# MICHAv40.net
KiCad netlist of a schematic drawn in EAGLE
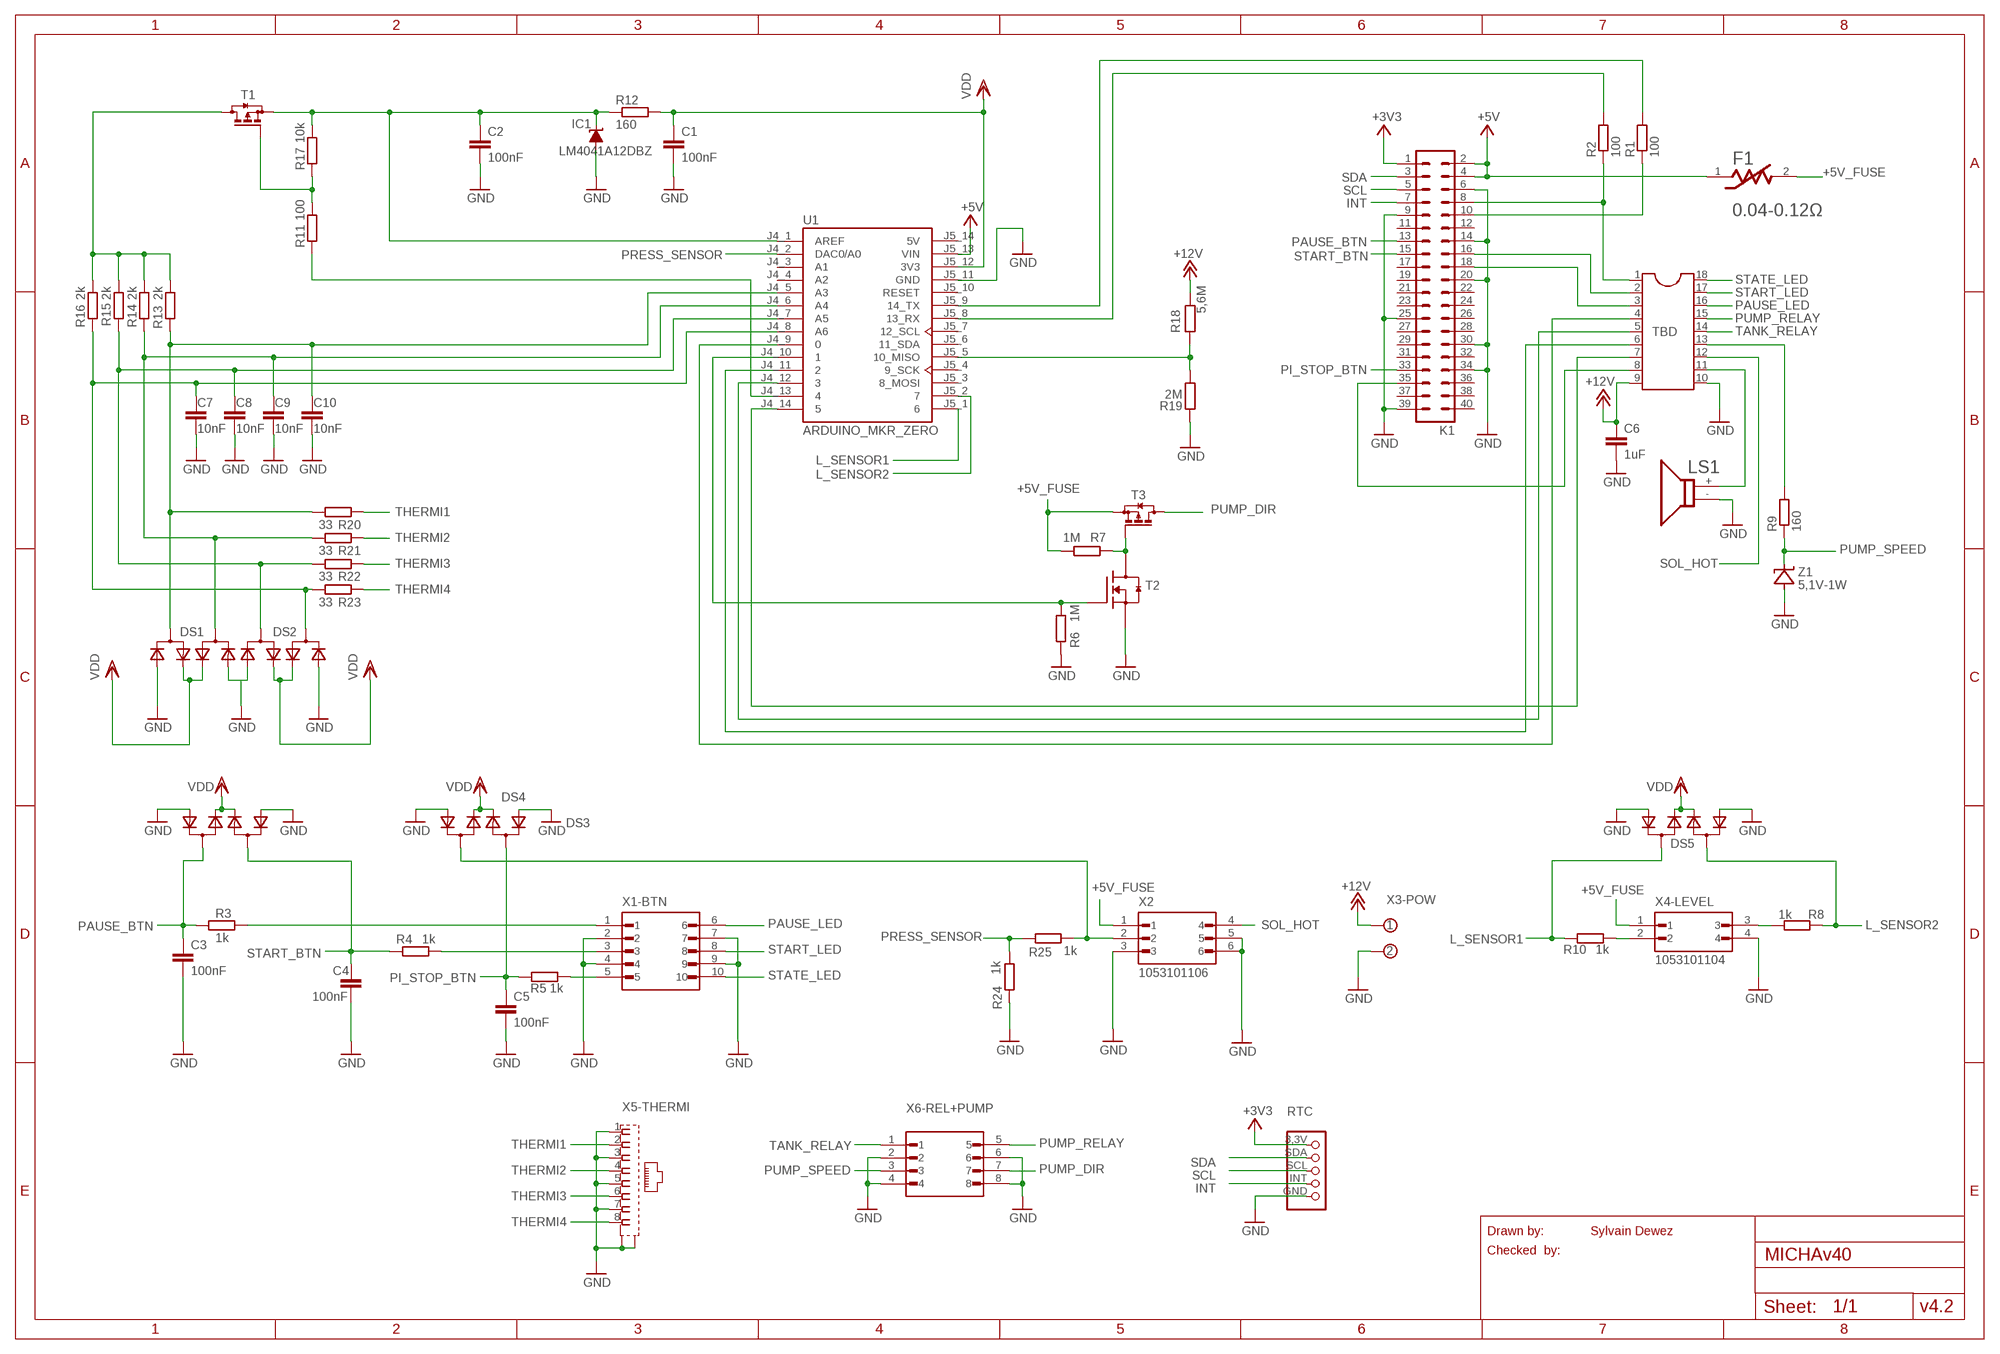
[diagram p0: schematic, sheet 1]

(export (version "E")
  (design (tool "Eeschema 10.0.6"))
  (components
    (comp (ref "C1")
      (value "100nF")
      (footprint "eagle-import:C1206")
      (libsource (lib "eagle-import") (part "C-EUC1206"))
    )
    (comp (ref "C2")
      (value "100nF")
      (footprint "eagle-import:C1206")
      (libsource (lib "eagle-import") (part "C-EUC1206"))
    )
    (comp (ref "C3")
      (value "100nF")
      (footprint "eagle-import:C1206")
      (libsource (lib "eagle-import") (part "C-EUC1206"))
    )
    (comp (ref "C4")
      (value "100nF")
      (footprint "eagle-import:C1206")
      (libsource (lib "eagle-import") (part "C-EUC1206"))
    )
    (comp (ref "C5")
      (value "100nF")
      (footprint "eagle-import:C1206")
      (libsource (lib "eagle-import") (part "C-EUC1206"))
    )
    (comp (ref "C6")
      (value "1uF")
      (footprint "eagle-import:C1206")
      (libsource (lib "eagle-import") (part "C-EUC1206"))
    )
    (comp (ref "C7")
      (value "10nF")
      (footprint "eagle-import:C1206")
      (libsource (lib "eagle-import") (part "C-EUC1206"))
    )
    (comp (ref "C8")
      (value "10nF")
      (footprint "eagle-import:C1206")
      (libsource (lib "eagle-import") (part "C-EUC1206"))
    )
    (comp (ref "C9")
      (value "10nF")
      (footprint "eagle-import:C1206")
      (libsource (lib "eagle-import") (part "C-EUC1206"))
    )
    (comp (ref "C10")
      (value "10nF")
      (footprint "eagle-import:C1206")
      (libsource (lib "eagle-import") (part "C-EUC1206"))
    )
    (comp (ref "DS1")
      (value "CMXSH2-4LSTRPBFREE")
      (footprint "eagle-import:CMXSH2-4LSTRPBFREE")
      (libsource (lib "eagle-import") (part "CMXSH2-4LSTRPBFREE"))
    )
    (comp (ref "DS2")
      (value "CMXSH2-4LSTRPBFREE")
      (footprint "eagle-import:CMXSH2-4LSTRPBFREE")
      (libsource (lib "eagle-import") (part "CMXSH2-4LSTRPBFREE"))
    )
    (comp (ref "DS3")
      (value "CMXSH2-4LSTRPBFREE")
      (footprint "eagle-import:CMXSH2-4LSTRPBFREE")
      (libsource (lib "eagle-import") (part "CMXSH2-4LSTRPBFREE"))
    )
    (comp (ref "DS4")
      (value "CMXSH2-4LSTRPBFREE")
      (footprint "eagle-import:CMXSH2-4LSTRPBFREE")
      (libsource (lib "eagle-import") (part "CMXSH2-4LSTRPBFREE"))
    )
    (comp (ref "DS5")
      (value "CMXSH2-4LSTRPBFREE")
      (footprint "eagle-import:CMXSH2-4LSTRPBFREE")
      (libsource (lib "eagle-import") (part "CMXSH2-4LSTRPBFREE"))
    )
    (comp (ref "F1")
      (value "LITTELFUSE_INC_1206L150THWRLITTELFUSE_INC_1206L150THWR_0_0")
      (footprint "eagle-import:LITTELFUSE_INC_1206L150THWR_0")
      (fields
        (field (name "DIGIKEY_PART_NUMBER") "F3372CT-ND")
        (field (name "MF") "Littelfuse Inc")
        (field (name "MOUSER_PART_NUMBER") "576-1206L150THWR")
      )
      (libsource (lib "eagle-import") (part "LITTELFUSE_INC_1206L150THWRLITTELFUSE_INC_1206L150THWR_0_0"))
    )
    (comp (ref "IC1")
      (value "LM4041A12DBZ")
      (footprint "eagle-import:DBZ_R-PDSO-G3")
      (fields (field (name "MPN") "LM4041A12IDBZR"))
      (libsource (lib "eagle-import") (part "LM4041DBZA12"))
    )
    (comp (ref "K1")
      (value "PIN20X2")
      (footprint "eagle-import:PIN_20X2")
      (libsource (lib "eagle-import") (part "PIN20X2"))
    )
    (comp (ref "LS1")
      (value "RSPRO-BUZZER-7800743")
      (footprint "eagle-import:RSPRO-BUZZER-7800743")
      (libsource (lib "eagle-import") (part "RSPRO-BUZZER-7800743"))
    )
    (comp (ref "R1")
      (value "100")
      (footprint "eagle-import:R1206")
      (libsource (lib "eagle-import") (part "resistor_R-EU_R1206"))
    )
    (comp (ref "R2")
      (value "100")
      (footprint "eagle-import:R1206")
      (libsource (lib "eagle-import") (part "resistor_R-EU_R1206"))
    )
    (comp (ref "R3")
      (value "1k")
      (footprint "eagle-import:R1206")
      (libsource (lib "eagle-import") (part "resistor_R-EU_R1206"))
    )
    (comp (ref "R4")
      (value "1k")
      (footprint "eagle-import:R1206")
      (libsource (lib "eagle-import") (part "resistor_R-EU_R1206"))
    )
    (comp (ref "R5")
      (value "1k")
      (footprint "eagle-import:R1206")
      (libsource (lib "eagle-import") (part "resistor_R-EU_R1206"))
    )
    (comp (ref "R6")
      (value "1M")
      (footprint "eagle-import:R1206")
      (libsource (lib "eagle-import") (part "resistor_R-EU_R1206"))
    )
    (comp (ref "R7")
      (value "1M")
      (footprint "eagle-import:R1206")
      (libsource (lib "eagle-import") (part "resistor_R-EU_R1206"))
    )
    (comp (ref "R8")
      (value "1k")
      (footprint "eagle-import:R1206")
      (libsource (lib "eagle-import") (part "resistor_R-EU_R1206"))
    )
    (comp (ref "R9")
      (value "160")
      (footprint "eagle-import:R1206")
      (libsource (lib "eagle-import") (part "R-EU_R1206"))
    )
    (comp (ref "R10")
      (value "1k")
      (footprint "eagle-import:R1206")
      (libsource (lib "eagle-import") (part "resistor_R-EU_R1206"))
    )
    (comp (ref "R11")
      (value "100")
      (footprint "eagle-import:R1206")
      (libsource (lib "eagle-import") (part "resistor_R-EU_R1206"))
    )
    (comp (ref "R12")
      (value "160")
      (footprint "eagle-import:R1206")
      (libsource (lib "eagle-import") (part "R-EU_R1206"))
    )
    (comp (ref "R13")
      (value "2k")
      (footprint "eagle-import:R1206")
      (libsource (lib "eagle-import") (part "resistor_R-EU_R1206"))
    )
    (comp (ref "R14")
      (value "2k")
      (footprint "eagle-import:R1206")
      (libsource (lib "eagle-import") (part "resistor_R-EU_R1206"))
    )
    (comp (ref "R15")
      (value "2k")
      (footprint "eagle-import:R1206")
      (libsource (lib "eagle-import") (part "resistor_R-EU_R1206"))
    )
    (comp (ref "R16")
      (value "2k")
      (footprint "eagle-import:R1206")
      (libsource (lib "eagle-import") (part "resistor_R-EU_R1206"))
    )
    (comp (ref "R17")
      (value "10k")
      (footprint "eagle-import:R1206")
      (libsource (lib "eagle-import") (part "resistor_R-EU_R1206"))
    )
    (comp (ref "R18")
      (value "5,6M")
      (footprint "eagle-import:R1206")
      (libsource (lib "eagle-import") (part "resistor_R-EU_R1206"))
    )
    (comp (ref "R19")
      (value "2M")
      (footprint "eagle-import:R1206")
      (libsource (lib "eagle-import") (part "resistor_R-EU_R1206"))
    )
    (comp (ref "R20")
      (value "33")
      (footprint "eagle-import:R1206")
      (libsource (lib "eagle-import") (part "resistor_R-EU_R1206"))
    )
    (comp (ref "R21")
      (value "33")
      (footprint "eagle-import:R1206")
      (libsource (lib "eagle-import") (part "resistor_R-EU_R1206"))
    )
    (comp (ref "R22")
      (value "33")
      (footprint "eagle-import:R1206")
      (libsource (lib "eagle-import") (part "resistor_R-EU_R1206"))
    )
    (comp (ref "R23")
      (value "33")
      (footprint "eagle-import:R1206")
      (libsource (lib "eagle-import") (part "resistor_R-EU_R1206"))
    )
    (comp (ref "R24")
      (value "1k")
      (footprint "eagle-import:R1206")
      (libsource (lib "eagle-import") (part "resistor_R-EU_R1206"))
    )
    (comp (ref "R25")
      (value "1k")
      (footprint "eagle-import:R1206")
      (libsource (lib "eagle-import") (part "resistor_R-EU_R1206"))
    )
    (comp (ref "RTC")
      (value "ODROID_C4_RTC_SHIELD")
      (footprint "eagle-import:ODROID_C4_RTC_SHIELD")
      (libsource (lib "eagle-import") (part "ODROID_C4_RTC_SHIELD"))
    )
    (comp (ref "T1")
      (value "BSS84")
      (footprint "eagle-import:SOT23")
      (libsource (lib "eagle-import") (part "BSS84"))
    )
    (comp (ref "T2")
      (value "MOSFET-NCH_SOT-23")
      (footprint "eagle-import:SOT95P280X135-3N")
      (libsource (lib "eagle-import") (part "MOSFET-NCH_SOT-23"))
    )
    (comp (ref "T3")
      (value "BSS84")
      (footprint "eagle-import:SOT23")
      (libsource (lib "eagle-import") (part "BSS84"))
    )
    (comp (ref "TBD")
      (value "DIL18S")
      (footprint "eagle-import:SOCKET-18")
      (libsource (lib "eagle-import") (part "DIL18S"))
    )
    (comp (ref "U1")
      (value "ARDUINO_MKR_ZERO")
      (footprint "eagle-import:MODULE_ARDUINO_MKR_ZERO")
      (fields (field (name "MF") "Arduino") (field (name "MP") "ARDUINO MKR ZERO"))
      (libsource (lib "eagle-import") (part "ARDUINO_MKR_ZERO"))
    )
    (comp (ref "X1-BTN")
      (value "1053101110")
      (footprint "eagle-import:MOLEX_1053101110")
      (fields (field (name "MANUFACTURER") "Molex"))
      (libsource (lib "eagle-import") (part "1053101110"))
    )
    (comp (ref "X2")
      (value "1053101106")
      (footprint "eagle-import:MOLEX_1053101106")
      (fields (field (name "MANUFACTURER") "Molex"))
      (libsource (lib "eagle-import") (part "1053101106"))
    )
    (comp (ref "X3-POW")
      (value "BUCHANAN_2_3.2MM")
      (footprint "eagle-import:BUCHANAN_2_3.5MM")
      (libsource (lib "eagle-import") (part "BUCHANAN_2_3.2MM"))
    )
    (comp (ref "X4-LEVEL")
      (value "1053101104")
      (footprint "eagle-import:MOLEX_1053101104")
      (fields (field (name "MANUFACTURER") "Molex"))
      (libsource (lib "eagle-import") (part "1053101104"))
    )
    (comp (ref "X5-THERMI")
      (value "SS-7188S-A-NF_V2")
      (footprint "eagle-import:BEL_SS-7188S-A-NF")
      (fields (field (name "MF") "Stewart Connector") (field (name "MP") "SS-7188S-A-NF"))
      (libsource (lib "eagle-import") (part "SS-7188S-A-NF_V2"))
    )
    (comp (ref "X6-REL+PUMP")
      (value "1053101108")
      (footprint "eagle-import:MOLEX_1053101108")
      (fields (field (name "MANUFACTURER") "Molex"))
      (libsource (lib "eagle-import") (part "1053101108"))
    )
    (comp (ref "Z1")
      (value "5,1V-1W")
      (footprint "eagle-import:ZENER_SMA")
      (libsource (lib "eagle-import") (part "ZENER_SMA"))
    )
  )
  (nets
    (net (code "1") (name "+3V3") (class "Default")
      (node (ref "K1") (pin "1") (pinfunction "1_1") (pintype "passive"))
      (node (ref "RTC") (pin "3,3V") (pinfunction "1_3,3V") (pintype "passive"))
    )
    (net (code "2") (name "+5V") (class "Default")
      (node (ref "F1") (pin "1") (pinfunction "1_1") (pintype "passive"))
      (node (ref "K1") (pin "2") (pinfunction "2_2") (pintype "passive"))
      (node (ref "K1") (pin "4") (pinfunction "4_4") (pintype "passive"))
      (node (ref "U1") (pin "J5_13") (pinfunction "VIN_J5_13") (pintype "power_in"))
    )
    (net (code "3") (name "+12V") (class "Default")
      (node (ref "C6") (pin "1") (pinfunction "1_1") (pintype "passive"))
      (node (ref "R18") (pin "2") (pinfunction "2_2") (pintype "passive"))
      (node (ref "TBD") (pin "9") (pinfunction "9_9") (pintype "passive"))
      (node (ref "X3-POW") (pin "1") (pinfunction "KL_1") (pintype "passive"))
    )
    (net (code "4") (name "/+5V_FUSE") (class "Default")
      (node (ref "F1") (pin "2") (pinfunction "2_2") (pintype "passive"))
      (node (ref "R7") (pin "2") (pinfunction "2_2") (pintype "passive"))
      (node (ref "T3") (pin "2") (pinfunction "S_2") (pintype "passive"))
      (node (ref "X2") (pin "1") (pinfunction "1_1") (pintype "passive"))
      (node (ref "X4-LEVEL") (pin "1") (pinfunction "1_1") (pintype "passive"))
    )
    (net (code "5") (name "/5V") (class "Default")
      (node (ref "U1") (pin "J5_14") (pinfunction "5V_J5_14") (pintype "power_in"))
    )
    (net (code "6") (name "/INT") (class "Default")
      (node (ref "K1") (pin "7") (pinfunction "7_7") (pintype "passive"))
      (node (ref "RTC") (pin "INT") (pinfunction "4_INT") (pintype "passive"))
    )
    (net (code "7") (name "/L_SENSOR1") (class "Default")
      (node (ref "DS5") (pin "5") (pinfunction "C_5") (pintype "passive"))
      (node (ref "R10") (pin "1") (pinfunction "1_1") (pintype "passive"))
      (node (ref "U1") (pin "J5_1") (pinfunction "6_J5_1") (pintype "bidirectional"))
    )
    (net (code "8") (name "/L_SENSOR2") (class "Default")
      (node (ref "DS5") (pin "2") (pinfunction "C1_2") (pintype "passive"))
      (node (ref "R8") (pin "1") (pinfunction "1_1") (pintype "passive"))
      (node (ref "U1") (pin "J5_2") (pinfunction "7_J5_2") (pintype "bidirectional"))
    )
    (net (code "9") (name "/PAUSE_BTN") (class "Default")
      (node (ref "C3") (pin "1") (pinfunction "1_1") (pintype "passive"))
      (node (ref "DS3") (pin "5") (pinfunction "C_5") (pintype "passive"))
      (node (ref "K1") (pin "13") (pinfunction "13_13") (pintype "passive"))
      (node (ref "R3") (pin "1") (pinfunction "1_1") (pintype "passive"))
    )
    (net (code "10") (name "/PAUSE_LED") (class "Default")
      (node (ref "TBD") (pin "16") (pinfunction "16_16") (pintype "passive"))
      (node (ref "X1-BTN") (pin "6") (pinfunction "6_6") (pintype "passive"))
    )
    (net (code "11") (name "/PI_STOP_BTN") (class "Default")
      (node (ref "C5") (pin "1") (pinfunction "1_1") (pintype "passive"))
      (node (ref "DS4") (pin "2") (pinfunction "C1_2") (pintype "passive"))
      (node (ref "K1") (pin "33") (pinfunction "33_33") (pintype "passive"))
      (node (ref "R5") (pin "1") (pinfunction "1_1") (pintype "passive"))
    )
    (net (code "12") (name "/PRESS_SENSOR") (class "Default")
      (node (ref "R24") (pin "2") (pinfunction "2_2") (pintype "passive"))
      (node (ref "R25") (pin "1") (pinfunction "1_1") (pintype "passive"))
      (node (ref "U1") (pin "J4_2") (pinfunction "DAC0/A0_J4_2") (pintype "bidirectional"))
    )
    (net (code "13") (name "/PUMP_DIR") (class "Default")
      (node (ref "T3") (pin "3") (pinfunction "D_3") (pintype "passive"))
      (node (ref "X6-REL+PUMP") (pin "7") (pinfunction "7_7") (pintype "passive"))
    )
    (net (code "14") (name "/PUMP_RELAY") (class "Default")
      (node (ref "TBD") (pin "15") (pinfunction "15_15") (pintype "passive"))
      (node (ref "X6-REL+PUMP") (pin "5") (pinfunction "5_5") (pintype "passive"))
    )
    (net (code "15") (name "/PUMP_SPEED") (class "Default")
      (node (ref "R9") (pin "1") (pinfunction "1_1") (pintype "passive"))
      (node (ref "X6-REL+PUMP") (pin "3") (pinfunction "3_3") (pintype "passive"))
      (node (ref "Z1") (pin "C") (pinfunction "C_C") (pintype "passive"))
    )
    (net (code "16") (name "/SCL") (class "Default")
      (node (ref "K1") (pin "5") (pinfunction "5_5") (pintype "passive"))
      (node (ref "RTC") (pin "SCL") (pinfunction "3_SCL") (pintype "passive"))
    )
    (net (code "17") (name "/SDA") (class "Default")
      (node (ref "K1") (pin "3") (pinfunction "3_3") (pintype "passive"))
      (node (ref "RTC") (pin "SDA") (pinfunction "2_SDA") (pintype "passive"))
    )
    (net (code "18") (name "/SOL_HOT") (class "Default")
      (node (ref "TBD") (pin "12") (pinfunction "12_12") (pintype "passive"))
      (node (ref "X2") (pin "4") (pinfunction "4_4") (pintype "passive"))
    )
    (net (code "19") (name "/START_BTN") (class "Default")
      (node (ref "C4") (pin "1") (pinfunction "1_1") (pintype "passive"))
      (node (ref "DS3") (pin "2") (pinfunction "C1_2") (pintype "passive"))
      (node (ref "K1") (pin "15") (pinfunction "15_15") (pintype "passive"))
      (node (ref "R4") (pin "1") (pinfunction "1_1") (pintype "passive"))
    )
    (net (code "20") (name "/START_LED") (class "Default")
      (node (ref "TBD") (pin "17") (pinfunction "17_17") (pintype "passive"))
      (node (ref "X1-BTN") (pin "8") (pinfunction "8_8") (pintype "passive"))
    )
    (net (code "21") (name "/STATE_LED") (class "Default")
      (node (ref "TBD") (pin "18") (pinfunction "18_18") (pintype "passive"))
      (node (ref "X1-BTN") (pin "10") (pinfunction "10_10") (pintype "passive"))
    )
    (net (code "22") (name "/TANK_RELAY") (class "Default")
      (node (ref "TBD") (pin "14") (pinfunction "14_14") (pintype "passive"))
      (node (ref "X6-REL+PUMP") (pin "1") (pinfunction "1_1") (pintype "passive"))
    )
    (net (code "23") (name "/THERMI1") (class "Default")
      (node (ref "R20") (pin "2") (pinfunction "2_2") (pintype "passive"))
      (node (ref "X5-THERMI") (pin "2") (pinfunction "2_2") (pintype "passive"))
    )
    (net (code "24") (name "/THERMI2") (class "Default")
      (node (ref "R21") (pin "2") (pinfunction "2_2") (pintype "passive"))
      (node (ref "X5-THERMI") (pin "4") (pinfunction "4_4") (pintype "passive"))
    )
    (net (code "25") (name "/THERMI3") (class "Default")
      (node (ref "R22") (pin "2") (pinfunction "2_2") (pintype "passive"))
      (node (ref "X5-THERMI") (pin "6") (pinfunction "6_6") (pintype "passive"))
    )
    (net (code "26") (name "/THERMI4") (class "Default")
      (node (ref "R23") (pin "2") (pinfunction "2_2") (pintype "passive"))
      (node (ref "X5-THERMI") (pin "8") (pinfunction "8_8") (pintype "passive"))
    )
    (net (code "27") (name "GND") (class "Default")
      (node (ref "C1") (pin "2") (pinfunction "2_2") (pintype "passive"))
      (node (ref "C10") (pin "2") (pinfunction "2_2") (pintype "passive"))
      (node (ref "C2") (pin "2") (pinfunction "2_2") (pintype "passive"))
      (node (ref "C3") (pin "2") (pinfunction "2_2") (pintype "passive"))
      (node (ref "C4") (pin "2") (pinfunction "2_2") (pintype "passive"))
      (node (ref "C5") (pin "2") (pinfunction "2_2") (pintype "passive"))
      (node (ref "C6") (pin "2") (pinfunction "2_2") (pintype "passive"))
      (node (ref "C7") (pin "2") (pinfunction "2_2") (pintype "passive"))
      (node (ref "C8") (pin "2") (pinfunction "2_2") (pintype "passive"))
      (node (ref "C9") (pin "2") (pinfunction "2_2") (pintype "passive"))
      (node (ref "DS1") (pin "1") (pinfunction "A3_1") (pintype "passive"))
      (node (ref "DS1") (pin "6") (pinfunction "A2_6") (pintype "passive"))
      (node (ref "DS2") (pin "1") (pinfunction "A3_1") (pintype "passive"))
      (node (ref "DS2") (pin "6") (pinfunction "A2_6") (pintype "passive"))
      (node (ref "DS3") (pin "1") (pinfunction "A3_1") (pintype "passive"))
      (node (ref "DS3") (pin "6") (pinfunction "A2_6") (pintype "passive"))
      (node (ref "DS4") (pin "1") (pinfunction "A3_1") (pintype "passive"))
      (node (ref "DS4") (pin "6") (pinfunction "A2_6") (pintype "passive"))
      (node (ref "DS5") (pin "1") (pinfunction "A3_1") (pintype "passive"))
      (node (ref "DS5") (pin "6") (pinfunction "A2_6") (pintype "passive"))
      (node (ref "IC1") (pin "2") (pinfunction "A_2") (pintype "passive"))
      (node (ref "K1") (pin "14") (pinfunction "14_14") (pintype "passive"))
      (node (ref "K1") (pin "20") (pinfunction "20_20") (pintype "passive"))
      (node (ref "K1") (pin "25") (pinfunction "25_25") (pintype "passive"))
      (node (ref "K1") (pin "30") (pinfunction "30_30") (pintype "passive"))
      (node (ref "K1") (pin "34") (pinfunction "34_34") (pintype "passive"))
      (node (ref "K1") (pin "39") (pinfunction "39_39") (pintype "passive"))
      (node (ref "K1") (pin "6") (pinfunction "6_6") (pintype "passive"))
      (node (ref "K1") (pin "9") (pinfunction "9_9") (pintype "passive"))
      (node (ref "LS1") (pin "-") (pinfunction "2_-") (pintype "passive"))
      (node (ref "R19") (pin "1") (pinfunction "1_1") (pintype "passive"))
      (node (ref "R24") (pin "1") (pinfunction "1_1") (pintype "passive"))
      (node (ref "R6") (pin "1") (pinfunction "1_1") (pintype "passive"))
      (node (ref "RTC") (pin "GND") (pinfunction "5_GND") (pintype "passive"))
      (node (ref "T2") (pin "2") (pinfunction "S_2") (pintype "passive"))
      (node (ref "TBD") (pin "10") (pinfunction "10_10") (pintype "passive"))
      (node (ref "U1") (pin "J5_11") (pinfunction "GND_J5_11") (pintype "power_in"))
      (node (ref "X1-BTN") (pin "2") (pinfunction "2_2") (pintype "passive"))
      (node (ref "X1-BTN") (pin "4") (pinfunction "4_4") (pintype "passive"))
      (node (ref "X1-BTN") (pin "7") (pinfunction "7_7") (pintype "passive"))
      (node (ref "X1-BTN") (pin "9") (pinfunction "9_9") (pintype "passive"))
      (node (ref "X2") (pin "3") (pinfunction "3_3") (pintype "passive"))
      (node (ref "X2") (pin "5") (pinfunction "5_5") (pintype "passive"))
      (node (ref "X2") (pin "6") (pinfunction "6_6") (pintype "passive"))
      (node (ref "X3-POW") (pin "2") (pinfunction "KL1_2") (pintype "passive"))
      (node (ref "X4-LEVEL") (pin "4") (pinfunction "4_4") (pintype "passive"))
      (node (ref "X5-THERMI") (pin "1") (pinfunction "1_1") (pintype "passive"))
      (node (ref "X5-THERMI") (pin "3") (pinfunction "3_3") (pintype "passive"))
      (node (ref "X5-THERMI") (pin "5") (pinfunction "5_5") (pintype "passive"))
      (node (ref "X5-THERMI") (pin "7") (pinfunction "7_7") (pintype "passive"))
      (node (ref "X5-THERMI") (pin "S1") (pinfunction "GND1_S1") (pintype "passive"))
      (node (ref "X5-THERMI") (pin "S2") (pinfunction "GND2_S2") (pintype "passive"))
      (node (ref "X6-REL+PUMP") (pin "2") (pinfunction "2_2") (pintype "passive"))
      (node (ref "X6-REL+PUMP") (pin "4") (pinfunction "4_4") (pintype "passive"))
      (node (ref "X6-REL+PUMP") (pin "6") (pinfunction "6_6") (pintype "passive"))
      (node (ref "X6-REL+PUMP") (pin "8") (pinfunction "8_8") (pintype "passive"))
      (node (ref "Z1") (pin "A") (pinfunction "A_A") (pintype "passive"))
    )
    (net (code "28") (name "Net-(DS1-C)") (class "Default")
      (node (ref "C9") (pin "1") (pinfunction "1_1") (pintype "passive"))
      (node (ref "DS1") (pin "5") (pinfunction "C_5") (pintype "passive"))
      (node (ref "R14") (pin "2") (pinfunction "2_2") (pintype "passive"))
      (node (ref "R21") (pin "1") (pinfunction "1_1") (pintype "passive"))
      (node (ref "U1") (pin "J4_6") (pinfunction "A4_J4_6") (pintype "bidirectional"))
    )
    (net (code "29") (name "Net-(DS1-C1)") (class "Default")
      (node (ref "C10") (pin "1") (pinfunction "1_1") (pintype "passive"))
      (node (ref "DS1") (pin "2") (pinfunction "C1_2") (pintype "passive"))
      (node (ref "R13") (pin "2") (pinfunction "2_2") (pintype "passive"))
      (node (ref "R20") (pin "1") (pinfunction "1_1") (pintype "passive"))
      (node (ref "U1") (pin "J4_5") (pinfunction "A3_J4_5") (pintype "bidirectional"))
    )
    (net (code "30") (name "Net-(DS2-C)") (class "Default")
      (node (ref "C7") (pin "1") (pinfunction "1_1") (pintype "passive"))
      (node (ref "DS2") (pin "5") (pinfunction "C_5") (pintype "passive"))
      (node (ref "R16") (pin "2") (pinfunction "2_2") (pintype "passive"))
      (node (ref "R23") (pin "1") (pinfunction "1_1") (pintype "passive"))
      (node (ref "U1") (pin "J4_8") (pinfunction "A6_J4_8") (pintype "bidirectional"))
    )
    (net (code "31") (name "Net-(DS2-C1)") (class "Default")
      (node (ref "C8") (pin "1") (pinfunction "1_1") (pintype "passive"))
      (node (ref "DS2") (pin "2") (pinfunction "C1_2") (pintype "passive"))
      (node (ref "R15") (pin "2") (pinfunction "2_2") (pintype "passive"))
      (node (ref "R22") (pin "1") (pinfunction "1_1") (pintype "passive"))
      (node (ref "U1") (pin "J4_7") (pinfunction "A5_J4_7") (pintype "bidirectional"))
    )
    (net (code "32") (name "Net-(DS4-C)") (class "Default")
      (node (ref "DS4") (pin "5") (pinfunction "C_5") (pintype "passive"))
      (node (ref "R25") (pin "2") (pinfunction "2_2") (pintype "passive"))
      (node (ref "X2") (pin "2") (pinfunction "2_2") (pintype "passive"))
    )
    (net (code "33") (name "Net-(IC1-C)") (class "Default")
      (node (ref "C2") (pin "1") (pinfunction "1_1") (pintype "passive"))
      (node (ref "IC1") (pin "1") (pinfunction "C_1") (pintype "passive"))
      (node (ref "R12") (pin "1") (pinfunction "1_1") (pintype "passive"))
      (node (ref "R17") (pin "2") (pinfunction "2_2") (pintype "passive"))
      (node (ref "T1") (pin "2") (pinfunction "S_2") (pintype "passive"))
      (node (ref "U1") (pin "J4_1") (pinfunction "AREF_J4_1") (pintype "bidirectional"))
    )
    (net (code "34") (name "Net-(K1-Pad8)") (class "Default")
      (node (ref "K1") (pin "8") (pinfunction "8_8") (pintype "passive"))
      (node (ref "R2") (pin "1") (pinfunction "1_1") (pintype "passive"))
      (node (ref "TBD") (pin "1") (pinfunction "1_1") (pintype "passive"))
    )
    (net (code "35") (name "Net-(K1-Pad10)") (class "Default")
      (node (ref "K1") (pin "10") (pinfunction "10_10") (pintype "passive"))
      (node (ref "R1") (pin "1") (pinfunction "1_1") (pintype "passive"))
    )
    (net (code "36") (name "Net-(K1-Pad16)") (class "Default")
      (node (ref "K1") (pin "16") (pinfunction "16_16") (pintype "passive"))
      (node (ref "TBD") (pin "2") (pinfunction "2_2") (pintype "passive"))
    )
    (net (code "37") (name "Net-(K1-Pad18)") (class "Default")
      (node (ref "K1") (pin "18") (pinfunction "18_18") (pintype "passive"))
      (node (ref "TBD") (pin "3") (pinfunction "3_3") (pintype "passive"))
    )
    (net (code "38") (name "Net-(K1-Pad35)") (class "Default")
      (node (ref "K1") (pin "35") (pinfunction "35_35") (pintype "passive"))
      (node (ref "TBD") (pin "8") (pinfunction "8_8") (pintype "passive"))
    )
    (net (code "39") (name "Net-(LS1-1)") (class "Default")
      (node (ref "LS1") (pin "+") (pinfunction "1_+") (pintype "passive"))
      (node (ref "TBD") (pin "11") (pinfunction "11_11") (pintype "passive"))
    )
    (net (code "40") (name "Net-(R3-Pad2)") (class "Default")
      (node (ref "R3") (pin "2") (pinfunction "2_2") (pintype "passive"))
      (node (ref "X1-BTN") (pin "1") (pinfunction "1_1") (pintype "passive"))
    )
    (net (code "41") (name "Net-(R4-Pad2)") (class "Default")
      (node (ref "R4") (pin "2") (pinfunction "2_2") (pintype "passive"))
      (node (ref "X1-BTN") (pin "3") (pinfunction "3_3") (pintype "passive"))
    )
    (net (code "42") (name "Net-(R5-Pad2)") (class "Default")
      (node (ref "R5") (pin "2") (pinfunction "2_2") (pintype "passive"))
      (node (ref "X1-BTN") (pin "5") (pinfunction "5_5") (pintype "passive"))
    )
    (net (code "43") (name "Net-(R8-Pad2)") (class "Default")
      (node (ref "R8") (pin "2") (pinfunction "2_2") (pintype "passive"))
      (node (ref "X4-LEVEL") (pin "3") (pinfunction "3_3") (pintype "passive"))
    )
    (net (code "44") (name "Net-(R9-Pad2)") (class "Default")
      (node (ref "R9") (pin "2") (pinfunction "2_2") (pintype "passive"))
      (node (ref "TBD") (pin "13") (pinfunction "13_13") (pintype "passive"))
    )
    (net (code "45") (name "Net-(R10-Pad2)") (class "Default")
      (node (ref "R10") (pin "2") (pinfunction "2_2") (pintype "passive"))
      (node (ref "X4-LEVEL") (pin "2") (pinfunction "2_2") (pintype "passive"))
    )
    (net (code "46") (name "Net-(T1-D)") (class "Default")
      (node (ref "R13") (pin "1") (pinfunction "1_1") (pintype "passive"))
      (node (ref "R14") (pin "1") (pinfunction "1_1") (pintype "passive"))
      (node (ref "R15") (pin "1") (pinfunction "1_1") (pintype "passive"))
      (node (ref "R16") (pin "1") (pinfunction "1_1") (pintype "passive"))
      (node (ref "T1") (pin "3") (pinfunction "D_3") (pintype "passive"))
    )
    (net (code "47") (name "Net-(T1-G)") (class "Default")
      (node (ref "R11") (pin "2") (pinfunction "2_2") (pintype "passive"))
      (node (ref "R17") (pin "1") (pinfunction "1_1") (pintype "passive"))
      (node (ref "T1") (pin "1") (pinfunction "G_1") (pintype "passive"))
    )
    (net (code "48") (name "Net-(T2-D)") (class "Default")
      (node (ref "R7") (pin "1") (pinfunction "1_1") (pintype "passive"))
      (node (ref "T2") (pin "3") (pinfunction "D_3") (pintype "passive"))
      (node (ref "T3") (pin "1") (pinfunction "G_1") (pintype "passive"))
    )
    (net (code "49") (name "Net-(T2-G)") (class "Default")
      (node (ref "R6") (pin "2") (pinfunction "2_2") (pintype "passive"))
      (node (ref "T2") (pin "1") (pinfunction "G_1") (pintype "passive"))
      (node (ref "U1") (pin "J4_10") (pinfunction "1_J4_10") (pintype "bidirectional"))
    )
    (net (code "50") (name "Net-(U1-0)") (class "Default")
      (node (ref "TBD") (pin "4") (pinfunction "4_4") (pintype "passive"))
      (node (ref "U1") (pin "J4_9") (pinfunction "0_J4_9") (pintype "bidirectional"))
    )
    (net (code "51") (name "Net-(U1-2)") (class "Default")
      (node (ref "TBD") (pin "6") (pinfunction "6_6") (pintype "passive"))
      (node (ref "U1") (pin "J4_11") (pinfunction "2_J4_11") (pintype "bidirectional"))
    )
    (net (code "52") (name "Net-(U1-3)") (class "Default")
      (node (ref "TBD") (pin "5") (pinfunction "5_5") (pintype "passive"))
      (node (ref "U1") (pin "J4_12") (pinfunction "3_J4_12") (pintype "bidirectional"))
    )
    (net (code "53") (name "Net-(U1-4)") (class "Default")
      (node (ref "R11") (pin "1") (pinfunction "1_1") (pintype "passive"))
      (node (ref "U1") (pin "J4_13") (pinfunction "4_J4_13") (pintype "bidirectional"))
    )
    (net (code "54") (name "Net-(U1-5)") (class "Default")
      (node (ref "TBD") (pin "7") (pinfunction "7_7") (pintype "passive"))
      (node (ref "U1") (pin "J4_14") (pinfunction "5_J4_14") (pintype "bidirectional"))
    )
    (net (code "55") (name "Net-(U1-10_MISO)") (class "Default")
      (node (ref "R18") (pin "1") (pinfunction "1_1") (pintype "passive"))
      (node (ref "R19") (pin "2") (pinfunction "2_2") (pintype "passive"))
      (node (ref "U1") (pin "J5_5") (pinfunction "10_MISO_J5_5") (pintype "bidirectional"))
    )
    (net (code "56") (name "Net-(U1-13_RX)") (class "Default")
      (node (ref "R2") (pin "2") (pinfunction "2_2") (pintype "passive"))
      (node (ref "U1") (pin "J5_8") (pinfunction "13_RX_J5_8") (pintype "input"))
    )
    (net (code "57") (name "Net-(U1-14_TX)") (class "Default")
      (node (ref "R1") (pin "2") (pinfunction "2_2") (pintype "passive"))
      (node (ref "U1") (pin "J5_9") (pinfunction "14_TX_J5_9") (pintype "output"))
    )
    (net (code "58") (name "VDD") (class "Default")
      (node (ref "C1") (pin "1") (pinfunction "1_1") (pintype "passive"))
      (node (ref "DS1") (pin "3") (pinfunction "A4_3") (pintype "passive"))
      (node (ref "DS1") (pin "4") (pinfunction "A1_4") (pintype "passive"))
      (node (ref "DS2") (pin "3") (pinfunction "A4_3") (pintype "passive"))
      (node (ref "DS2") (pin "4") (pinfunction "A1_4") (pintype "passive"))
      (node (ref "DS3") (pin "3") (pinfunction "A4_3") (pintype "passive"))
      (node (ref "DS3") (pin "4") (pinfunction "A1_4") (pintype "passive"))
      (node (ref "DS4") (pin "3") (pinfunction "A4_3") (pintype "passive"))
      (node (ref "DS4") (pin "4") (pinfunction "A1_4") (pintype "passive"))
      (node (ref "DS5") (pin "3") (pinfunction "A4_3") (pintype "passive"))
      (node (ref "DS5") (pin "4") (pinfunction "A1_4") (pintype "passive"))
      (node (ref "R12") (pin "2") (pinfunction "2_2") (pintype "passive"))
      (node (ref "U1") (pin "J5_12") (pinfunction "3V3_J5_12") (pintype "power_in"))
    )
    (net (code "59") (name "unconnected-(K1-Pad11)") (class "Default")
      (node (ref "K1") (pin "11") (pinfunction "11_11") (pintype "passive"))
    )
    (net (code "60") (name "unconnected-(K1-Pad12)") (class "Default")
      (node (ref "K1") (pin "12") (pinfunction "12_12") (pintype "passive"))
    )
    (net (code "61") (name "unconnected-(K1-Pad17)") (class "Default")
      (node (ref "K1") (pin "17") (pinfunction "17_17") (pintype "passive"))
    )
    (net (code "62") (name "unconnected-(K1-Pad19)") (class "Default")
      (node (ref "K1") (pin "19") (pinfunction "19_19") (pintype "passive"))
    )
    (net (code "63") (name "unconnected-(K1-Pad21)") (class "Default")
      (node (ref "K1") (pin "21") (pinfunction "21_21") (pintype "passive"))
    )
    (net (code "64") (name "unconnected-(K1-Pad22)") (class "Default")
      (node (ref "K1") (pin "22") (pinfunction "22_22") (pintype "passive"))
    )
    (net (code "65") (name "unconnected-(K1-Pad23)") (class "Default")
      (node (ref "K1") (pin "23") (pinfunction "23_23") (pintype "passive"))
    )
    (net (code "66") (name "unconnected-(K1-Pad24)") (class "Default")
      (node (ref "K1") (pin "24") (pinfunction "24_24") (pintype "passive"))
    )
    (net (code "67") (name "unconnected-(K1-Pad26)") (class "Default")
      (node (ref "K1") (pin "26") (pinfunction "26_26") (pintype "passive"))
    )
    (net (code "68") (name "unconnected-(K1-Pad27)") (class "Default")
      (node (ref "K1") (pin "27") (pinfunction "27_27") (pintype "passive"))
    )
    (net (code "69") (name "unconnected-(K1-Pad28)") (class "Default")
      (node (ref "K1") (pin "28") (pinfunction "28_28") (pintype "passive"))
    )
    (net (code "70") (name "unconnected-(K1-Pad29)") (class "Default")
      (node (ref "K1") (pin "29") (pinfunction "29_29") (pintype "passive"))
    )
    (net (code "71") (name "unconnected-(K1-Pad31)") (class "Default")
      (node (ref "K1") (pin "31") (pinfunction "31_31") (pintype "passive"))
    )
    (net (code "72") (name "unconnected-(K1-Pad32)") (class "Default")
      (node (ref "K1") (pin "32") (pinfunction "32_32") (pintype "passive"))
    )
    (net (code "73") (name "unconnected-(K1-Pad36)") (class "Default")
      (node (ref "K1") (pin "36") (pinfunction "36_36") (pintype "passive"))
    )
    (net (code "74") (name "unconnected-(K1-Pad37)") (class "Default")
      (node (ref "K1") (pin "37") (pinfunction "37_37") (pintype "passive"))
    )
    (net (code "75") (name "unconnected-(K1-Pad38)") (class "Default")
      (node (ref "K1") (pin "38") (pinfunction "38_38") (pintype "passive"))
    )
    (net (code "76") (name "unconnected-(K1-Pad40)") (class "Default")
      (node (ref "K1") (pin "40") (pinfunction "40_40") (pintype "passive"))
    )
    (net (code "77") (name "unconnected-(U1-8_MOSI-PadJ5_3)") (class "Default")
      (node (ref "U1") (pin "J5_3") (pinfunction "8_MOSI_J5_3") (pintype "bidirectional"))
    )
    (net (code "78") (name "unconnected-(U1-9_SCK-PadJ5_4)") (class "Default")
      (node (ref "U1") (pin "J5_4") (pinfunction "9_SCK_J5_4") (pintype "bidirectional"))
    )
    (net (code "79") (name "unconnected-(U1-11_SDA-PadJ5_6)") (class "Default")
      (node (ref "U1") (pin "J5_6") (pinfunction "11_SDA_J5_6") (pintype "bidirectional"))
    )
    (net (code "80") (name "unconnected-(U1-12_SCL-PadJ5_7)") (class "Default")
      (node (ref "U1") (pin "J5_7") (pinfunction "12_SCL_J5_7") (pintype "bidirectional"))
    )
    (net (code "81") (name "unconnected-(U1-A1-PadJ4_3)") (class "Default")
      (node (ref "U1") (pin "J4_3") (pinfunction "A1_J4_3") (pintype "bidirectional"))
    )
    (net (code "82") (name "unconnected-(U1-A2-PadJ4_4)") (class "Default")
      (node (ref "U1") (pin "J4_4") (pinfunction "A2_J4_4") (pintype "bidirectional"))
    )
    (net (code "83") (name "unconnected-(U1-RESET-PadJ5_10)") (class "Default")
      (node (ref "U1") (pin "J5_10") (pinfunction "RESET_J5_10") (pintype "bidirectional"))
    )
  )
)
